# Rfid.net
KiCad netlist of a schematic drawn in EAGLE
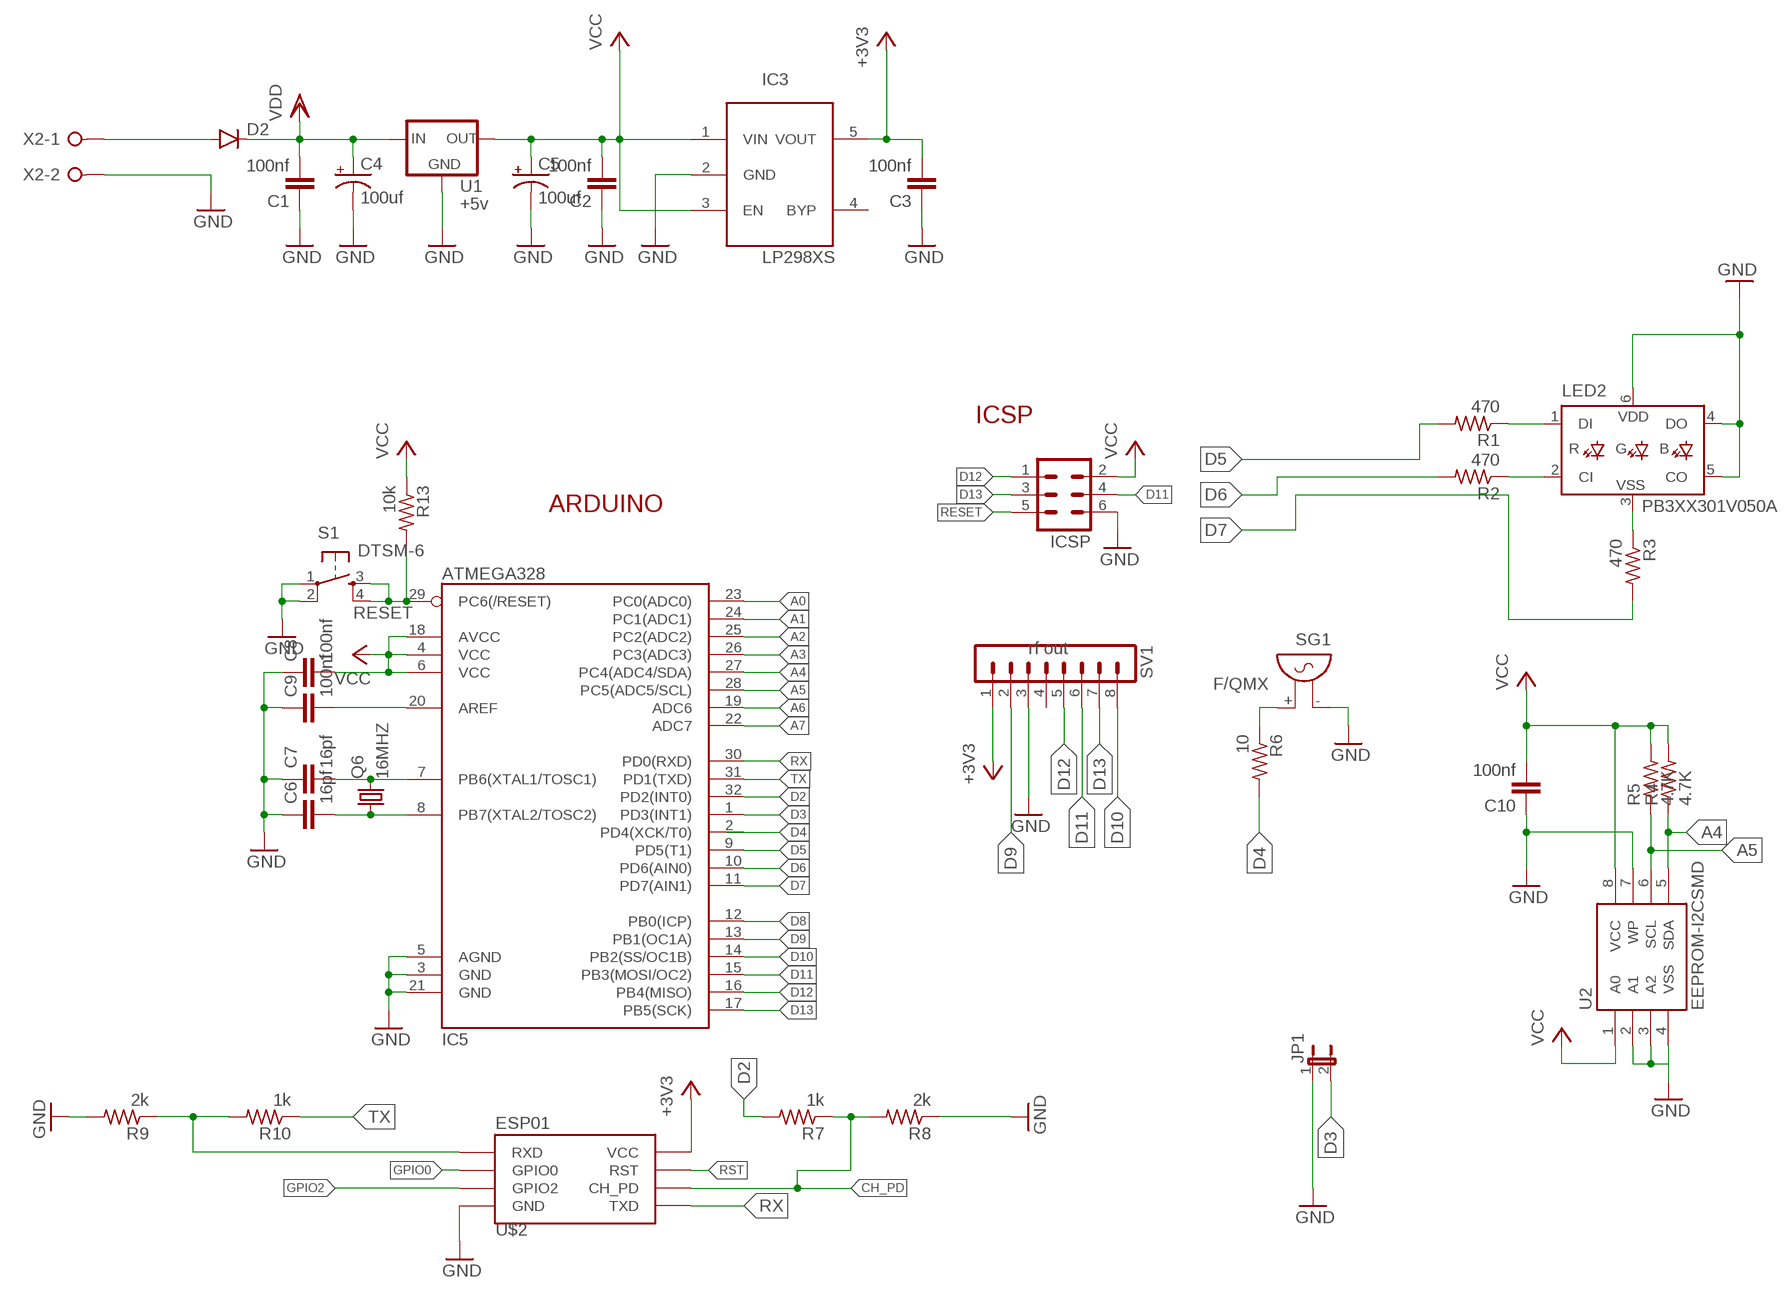
[diagram p0: schematic, sheet 1]

(export (version "E")
  (design (tool "Eeschema 10.0.6"))
  (components
    (comp (ref "C1")
      (value "100nf")
      (footprint "eagle-import:C0805")
      (libsource (lib "eagle-import") (part "C-EUC0805"))
    )
    (comp (ref "C2")
      (value "100nf")
      (footprint "eagle-import:C0805")
      (libsource (lib "eagle-import") (part "C-EUC0805"))
    )
    (comp (ref "C3")
      (value "100nf")
      (footprint "eagle-import:C0805")
      (libsource (lib "eagle-import") (part "C-EUC0805"))
    )
    (comp (ref "C4")
      (value "100uf")
      (footprint "eagle-import:PANASONIC_D")
      (libsource (lib "eagle-import") (part "CAP_POLD"))
    )
    (comp (ref "C5")
      (value "100uf")
      (footprint "eagle-import:PANASONIC_D")
      (libsource (lib "eagle-import") (part "CAP_POLD"))
    )
    (comp (ref "C6")
      (value "16pf")
      (footprint "eagle-import:C0805")
      (libsource (lib "eagle-import") (part "C-EUC0805"))
    )
    (comp (ref "C7")
      (value "16pf")
      (footprint "eagle-import:C0805")
      (libsource (lib "eagle-import") (part "C-EUC0805"))
    )
    (comp (ref "C8")
      (value "100nf")
      (footprint "eagle-import:C0805")
      (libsource (lib "eagle-import") (part "C-EUC0805"))
    )
    (comp (ref "C9")
      (value "100nf")
      (footprint "eagle-import:C0805")
      (libsource (lib "eagle-import") (part "C-EUC0805"))
    )
    (comp (ref "C10")
      (value "100nf")
      (footprint "eagle-import:C0805")
      (libsource (lib "eagle-import") (part "C-EUC0805"))
    )
    (comp (ref "D2")
      (value "DIODESMA-ALT")
      (footprint "eagle-import:SMA-DIODE_ALT")
      (libsource (lib "eagle-import") (part "DIODESMA-ALT"))
    )
    (comp (ref "IC3")
      (value "LP298XS")
      (footprint "eagle-import:SOT23-5L")
      (libsource (lib "eagle-import") (part "LP298XS"))
    )
    (comp (ref "IC5")
      (value "ATMEGA328")
      (footprint "eagle-import:TQFP32-08")
      (libsource (lib "eagle-import") (part "ATMEGA168"))
    )
    (comp (ref "ICSP")
      (value "ML6")
      (footprint "eagle-import:ML6")
      (libsource (lib "eagle-import") (part "ML6"))
    )
    (comp (ref "JP1")
      (value "JUMPER-2PTH")
      (footprint "eagle-import:1X02")
      (libsource (lib "eagle-import") (part "JUMPER-2PTH"))
    )
    (comp (ref "LED2")
      (value "PB3XX301V050A")
      (footprint "eagle-import:PB3XX301V050A")
      (libsource (lib "eagle-import") (part "PB3XX301V050A"))
    )
    (comp (ref "Q6")
      (value "16MHZ")
      (footprint "eagle-import:HC49_S")
      (libsource (lib "eagle-import") (part "CRYSTALHC49S"))
    )
    (comp (ref "R1")
      (value "470")
      (footprint "eagle-import:R0805")
      (libsource (lib "eagle-import") (part "R-US_R0805"))
    )
    (comp (ref "R2")
      (value "470")
      (footprint "eagle-import:R0805")
      (libsource (lib "eagle-import") (part "R-US_R0805"))
    )
    (comp (ref "R3")
      (value "470")
      (footprint "eagle-import:R0805")
      (libsource (lib "eagle-import") (part "R-US_R0805"))
    )
    (comp (ref "R4")
      (value "4.7K")
      (footprint "eagle-import:R0805")
      (libsource (lib "eagle-import") (part "R-US_R0805"))
    )
    (comp (ref "R5")
      (value "4.7K")
      (footprint "eagle-import:R0805")
      (libsource (lib "eagle-import") (part "R-US_R0805"))
    )
    (comp (ref "R6")
      (value "10")
      (footprint "eagle-import:R0805")
      (libsource (lib "eagle-import") (part "R-US_R0805"))
    )
    (comp (ref "R7")
      (value "1k")
      (footprint "eagle-import:R0805")
      (libsource (lib "eagle-import") (part "R-US_R0805"))
    )
    (comp (ref "R8")
      (value "2k")
      (footprint "eagle-import:R0805")
      (libsource (lib "eagle-import") (part "R-US_R0805"))
    )
    (comp (ref "R9")
      (value "2k")
      (footprint "eagle-import:R0805")
      (libsource (lib "eagle-import") (part "R-US_R0805"))
    )
    (comp (ref "R10")
      (value "1k")
      (footprint "eagle-import:R0805")
      (libsource (lib "eagle-import") (part "R-US_R0805"))
    )
    (comp (ref "R13")
      (value "10k")
      (footprint "eagle-import:R0805")
      (libsource (lib "eagle-import") (part "R-US_R0805"))
    )
    (comp (ref "S1")
      (value "DTSM-6")
      (footprint "eagle-import:DTSM-6")
      (libsource (lib "eagle-import") (part "DTSM-6"))
    )
    (comp (ref "SG1")
      (value "F/QMX")
      (footprint "eagle-import:F_QMX")
      (libsource (lib "eagle-import") (part "F/QMX"))
    )
    (comp (ref "SV1")
      (value "MA08-1")
      (footprint "eagle-import:MA08-1")
      (libsource (lib "eagle-import") (part "MA08-1"))
    )
    (comp (ref "U$2")
      (value "ESP01")
      (footprint "eagle-import:ESP01")
      (libsource (lib "eagle-import") (part "ESP01"))
    )
    (comp (ref "U1")
      (value "+5v")
      (footprint "eagle-import:TO-252")
      (libsource (lib "eagle-import") (part "V_REG_78XX7812"))
    )
    (comp (ref "U2")
      (value "EEPROM-I2CSMD")
      (footprint "eagle-import:SO08")
      (libsource (lib "eagle-import") (part "EEPROM-I2CSMD"))
    )
    (comp (ref "X2")
      (value "W237-02P")
      (footprint "eagle-import:W237-132")
      (libsource (lib "eagle-import") (part "W237-02P"))
    )
  )
  (nets
    (net (code "1") (name "+3V3") (class "Default")
      (node (ref "C3") (pin "2") (pinfunction "2_2") (pintype "passive"))
      (node (ref "IC3") (pin "5") (pinfunction "VOUT_5") (pintype "bidirectional"))
      (node (ref "SV1") (pin "1") (pinfunction "1_1") (pintype "passive"))
      (node (ref "U$2") (pin "VCC") (pinfunction "VCC_VCC") (pintype "bidirectional"))
    )
    (net (code "2") (name "A0") (class "Default")
      (node (ref "IC5") (pin "23") (pinfunction "PC0(ADC0)_23") (pintype "bidirectional"))
    )
    (net (code "3") (name "A1") (class "Default")
      (node (ref "IC5") (pin "24") (pinfunction "PC1(ADC1)_24") (pintype "bidirectional"))
    )
    (net (code "4") (name "A2") (class "Default")
      (node (ref "IC5") (pin "25") (pinfunction "PC2(ADC2)_25") (pintype "bidirectional"))
    )
    (net (code "5") (name "A3") (class "Default")
      (node (ref "IC5") (pin "26") (pinfunction "PC3(ADC3)_26") (pintype "bidirectional"))
    )
    (net (code "6") (name "A4") (class "Default")
      (node (ref "IC5") (pin "27") (pinfunction "PC4(ADC4/SDA)_27") (pintype "bidirectional"))
      (node (ref "R4") (pin "1") (pinfunction "1_1") (pintype "passive"))
      (node (ref "U2") (pin "5") (pinfunction "SDA_5") (pintype "bidirectional"))
    )
    (net (code "7") (name "A5") (class "Default")
      (node (ref "IC5") (pin "28") (pinfunction "PC5(ADC5/SCL)_28") (pintype "bidirectional"))
      (node (ref "R5") (pin "1") (pinfunction "1_1") (pintype "passive"))
      (node (ref "U2") (pin "6") (pinfunction "SCL_6") (pintype "bidirectional"))
    )
    (net (code "8") (name "A6") (class "Default")
      (node (ref "IC5") (pin "19") (pinfunction "ADC6_19") (pintype "bidirectional"))
    )
    (net (code "9") (name "A7") (class "Default")
      (node (ref "IC5") (pin "22") (pinfunction "ADC7_22") (pintype "bidirectional"))
    )
    (net (code "10") (name "CH_PD") (class "Default")
      (node (ref "R7") (pin "1") (pinfunction "1_1") (pintype "passive"))
      (node (ref "R8") (pin "2") (pinfunction "2_2") (pintype "passive"))
      (node (ref "U$2") (pin "CH_PD") (pinfunction "CH_PD_CH_PD") (pintype "bidirectional"))
    )
    (net (code "11") (name "D2") (class "Default")
      (node (ref "IC5") (pin "32") (pinfunction "PD2(INT0)_32") (pintype "bidirectional"))
      (node (ref "R7") (pin "2") (pinfunction "2_2") (pintype "passive"))
    )
    (net (code "12") (name "D3") (class "Default")
      (node (ref "IC5") (pin "1") (pinfunction "PD3(INT1)_1") (pintype "bidirectional"))
      (node (ref "JP1") (pin "2") (pinfunction "2_2") (pintype "passive"))
    )
    (net (code "13") (name "D4") (class "Default")
      (node (ref "IC5") (pin "2") (pinfunction "PD4(XCK/T0)_2") (pintype "bidirectional"))
      (node (ref "R6") (pin "2") (pinfunction "2_2") (pintype "passive"))
    )
    (net (code "14") (name "D5") (class "Default")
      (node (ref "IC5") (pin "9") (pinfunction "PD5(T1)_9") (pintype "bidirectional"))
      (node (ref "R1") (pin "2") (pinfunction "2_2") (pintype "passive"))
    )
    (net (code "15") (name "D6") (class "Default")
      (node (ref "IC5") (pin "10") (pinfunction "PD6(AIN0)_10") (pintype "bidirectional"))
      (node (ref "R2") (pin "2") (pinfunction "2_2") (pintype "passive"))
    )
    (net (code "16") (name "D7") (class "Default")
      (node (ref "IC5") (pin "11") (pinfunction "PD7(AIN1)_11") (pintype "bidirectional"))
      (node (ref "R3") (pin "2") (pinfunction "2_2") (pintype "passive"))
    )
    (net (code "17") (name "D8") (class "Default")
      (node (ref "IC5") (pin "12") (pinfunction "PB0(ICP)_12") (pintype "bidirectional"))
    )
    (net (code "18") (name "D9") (class "Default")
      (node (ref "IC5") (pin "13") (pinfunction "PB1(OC1A)_13") (pintype "bidirectional"))
      (node (ref "SV1") (pin "2") (pinfunction "2_2") (pintype "passive"))
    )
    (net (code "19") (name "D10") (class "Default")
      (node (ref "IC5") (pin "14") (pinfunction "PB2(SS/OC1B)_14") (pintype "bidirectional"))
      (node (ref "SV1") (pin "8") (pinfunction "8_8") (pintype "passive"))
    )
    (net (code "20") (name "D11") (class "Default")
      (node (ref "IC5") (pin "15") (pinfunction "PB3(MOSI/OC2)_15") (pintype "bidirectional"))
      (node (ref "ICSP") (pin "4") (pinfunction "4_4") (pintype "passive"))
      (node (ref "SV1") (pin "6") (pinfunction "6_6") (pintype "passive"))
    )
    (net (code "21") (name "D12") (class "Default")
      (node (ref "IC5") (pin "16") (pinfunction "PB4(MISO)_16") (pintype "bidirectional"))
      (node (ref "ICSP") (pin "1") (pinfunction "1_1") (pintype "passive"))
      (node (ref "SV1") (pin "5") (pinfunction "5_5") (pintype "passive"))
    )
    (net (code "22") (name "D13") (class "Default")
      (node (ref "IC5") (pin "17") (pinfunction "PB5(SCK)_17") (pintype "bidirectional"))
      (node (ref "ICSP") (pin "3") (pinfunction "3_3") (pintype "passive"))
      (node (ref "SV1") (pin "7") (pinfunction "7_7") (pintype "passive"))
    )
    (net (code "23") (name "GND") (class "Default")
      (node (ref "C1") (pin "1") (pinfunction "1_1") (pintype "passive"))
      (node (ref "C10") (pin "1") (pinfunction "1_1") (pintype "passive"))
      (node (ref "C2") (pin "1") (pinfunction "1_1") (pintype "passive"))
      (node (ref "C3") (pin "1") (pinfunction "1_1") (pintype "passive"))
      (node (ref "C4") (pin "-") (pinfunction "-_-") (pintype "passive"))
      (node (ref "C5") (pin "-") (pinfunction "-_-") (pintype "passive"))
      (node (ref "C6") (pin "1") (pinfunction "1_1") (pintype "passive"))
      (node (ref "C7") (pin "1") (pinfunction "1_1") (pintype "passive"))
      (node (ref "C8") (pin "1") (pinfunction "1_1") (pintype "passive"))
      (node (ref "C9") (pin "1") (pinfunction "1_1") (pintype "passive"))
      (node (ref "IC3") (pin "2") (pinfunction "GND_2") (pintype "bidirectional"))
      (node (ref "IC5") (pin "21") (pinfunction "GND_21") (pintype "bidirectional"))
      (node (ref "IC5") (pin "3") (pinfunction "GND_3") (pintype "bidirectional"))
      (node (ref "IC5") (pin "5") (pinfunction "AGND_5") (pintype "bidirectional"))
      (node (ref "ICSP") (pin "6") (pinfunction "6_6") (pintype "passive"))
      (node (ref "JP1") (pin "1") (pinfunction "1_1") (pintype "passive"))
      (node (ref "LED2") (pin "4") (pinfunction "DO_4") (pintype "output"))
      (node (ref "LED2") (pin "5") (pinfunction "CO_5") (pintype "output"))
      (node (ref "LED2") (pin "6") (pinfunction "VDD_6") (pintype "power_in"))
      (node (ref "R8") (pin "1") (pinfunction "1_1") (pintype "passive"))
      (node (ref "R9") (pin "2") (pinfunction "2_2") (pintype "passive"))
      (node (ref "S1") (pin "1") (pinfunction "1_1") (pintype "passive"))
      (node (ref "S1") (pin "2") (pinfunction "2_2") (pintype "passive"))
      (node (ref "SG1") (pin "-") (pinfunction "1_-") (pintype "passive"))
      (node (ref "SV1") (pin "3") (pinfunction "3_3") (pintype "passive"))
      (node (ref "U$2") (pin "GND") (pinfunction "GND_GND") (pintype "bidirectional"))
      (node (ref "U1") (pin "3") (pinfunction "GND_3") (pintype "input"))
      (node (ref "U2") (pin "2") (pinfunction "A1_2") (pintype "bidirectional"))
      (node (ref "U2") (pin "3") (pinfunction "A2_3") (pintype "bidirectional"))
      (node (ref "U2") (pin "4") (pinfunction "VSS_4") (pintype "power_in"))
      (node (ref "U2") (pin "7") (pinfunction "WP_7") (pintype "bidirectional"))
      (node (ref "X2") (pin "2") (pinfunction "KL_2") (pintype "passive"))
    )
    (net (code "24") (name "GPIO0") (class "Default")
      (node (ref "U$2") (pin "GPIO0") (pinfunction "GPIO0_GPIO0") (pintype "bidirectional"))
    )
    (net (code "25") (name "GPIO2") (class "Default")
      (node (ref "U$2") (pin "GPIO2") (pinfunction "GPIO2_GPIO2") (pintype "bidirectional"))
    )
    (net (code "26") (name "Net-(IC5-AREF)") (class "Default")
      (node (ref "C9") (pin "2") (pinfunction "2_2") (pintype "passive"))
      (node (ref "IC5") (pin "20") (pinfunction "AREF_20") (pintype "bidirectional"))
    )
    (net (code "27") (name "Net-(IC5-PB6(XTAL1{slash}TOSC1))") (class "Default")
      (node (ref "C7") (pin "2") (pinfunction "2_2") (pintype "passive"))
      (node (ref "IC5") (pin "7") (pinfunction "PB6(XTAL1/TOSC1)_7") (pintype "bidirectional"))
      (node (ref "Q6") (pin "2") (pinfunction "2_2") (pintype "passive"))
    )
    (net (code "28") (name "Net-(IC5-PB7(XTAL2{slash}TOSC2))") (class "Default")
      (node (ref "C6") (pin "2") (pinfunction "2_2") (pintype "passive"))
      (node (ref "IC5") (pin "8") (pinfunction "PB7(XTAL2/TOSC2)_8") (pintype "bidirectional"))
      (node (ref "Q6") (pin "1") (pinfunction "1_1") (pintype "passive"))
    )
    (net (code "29") (name "Net-(LED2-CI)") (class "Default")
      (node (ref "LED2") (pin "2") (pinfunction "CI_2") (pintype "input"))
      (node (ref "R2") (pin "1") (pinfunction "1_1") (pintype "passive"))
    )
    (net (code "30") (name "Net-(LED2-DI)") (class "Default")
      (node (ref "LED2") (pin "1") (pinfunction "DI_1") (pintype "input"))
      (node (ref "R1") (pin "1") (pinfunction "1_1") (pintype "passive"))
    )
    (net (code "31") (name "Net-(LED2-VSS)") (class "Default")
      (node (ref "LED2") (pin "3") (pinfunction "VSS_3") (pintype "power_in"))
      (node (ref "R3") (pin "1") (pinfunction "1_1") (pintype "passive"))
    )
    (net (code "32") (name "Net-(SG1-2)") (class "Default")
      (node (ref "R6") (pin "1") (pinfunction "1_1") (pintype "passive"))
      (node (ref "SG1") (pin "+") (pinfunction "2_+") (pintype "passive"))
    )
    (net (code "33") (name "Net-(U$2-RXD)") (class "Default")
      (node (ref "R10") (pin "2") (pinfunction "2_2") (pintype "passive"))
      (node (ref "R9") (pin "1") (pinfunction "1_1") (pintype "passive"))
      (node (ref "U$2") (pin "RX") (pinfunction "RXD_RX") (pintype "bidirectional"))
    )
    (net (code "34") (name "Net-(X2A-KL)") (class "Default")
      (node (ref "D2") (pin "A") (pinfunction "A_A") (pintype "passive"))
      (node (ref "X2") (pin "1") (pinfunction "KL_1") (pintype "passive"))
    )
    (net (code "35") (name "RESET") (class "Default")
      (node (ref "IC5") (pin "29") (pinfunction "PC6(/RESET)_29") (pintype "bidirectional"))
      (node (ref "ICSP") (pin "5") (pinfunction "5_5") (pintype "passive"))
      (node (ref "R13") (pin "2") (pinfunction "2_2") (pintype "passive"))
      (node (ref "S1") (pin "3") (pinfunction "3_3") (pintype "passive"))
      (node (ref "S1") (pin "4") (pinfunction "4_4") (pintype "passive"))
    )
    (net (code "36") (name "RST") (class "Default")
      (node (ref "U$2") (pin "RST") (pinfunction "RST_RST") (pintype "bidirectional"))
    )
    (net (code "37") (name "RX") (class "Default")
      (node (ref "IC5") (pin "30") (pinfunction "PD0(RXD)_30") (pintype "bidirectional"))
      (node (ref "U$2") (pin "TX") (pinfunction "TXD_TX") (pintype "bidirectional"))
    )
    (net (code "38") (name "TX") (class "Default")
      (node (ref "IC5") (pin "31") (pinfunction "PD1(TXD)_31") (pintype "bidirectional"))
      (node (ref "R10") (pin "1") (pinfunction "1_1") (pintype "passive"))
    )
    (net (code "39") (name "VCC") (class "Default")
      (node (ref "C10") (pin "2") (pinfunction "2_2") (pintype "passive"))
      (node (ref "C2") (pin "2") (pinfunction "2_2") (pintype "passive"))
      (node (ref "C5") (pin "+") (pinfunction "+_+") (pintype "passive"))
      (node (ref "C8") (pin "2") (pinfunction "2_2") (pintype "passive"))
      (node (ref "IC3") (pin "1") (pinfunction "VIN_1") (pintype "bidirectional"))
      (node (ref "IC3") (pin "3") (pinfunction "EN_3") (pintype "bidirectional"))
      (node (ref "IC5") (pin "18") (pinfunction "AVCC_18") (pintype "bidirectional"))
      (node (ref "IC5") (pin "4") (pinfunction "VCC_4") (pintype "bidirectional"))
      (node (ref "IC5") (pin "6") (pinfunction "VCC_6") (pintype "bidirectional"))
      (node (ref "ICSP") (pin "2") (pinfunction "2_2") (pintype "passive"))
      (node (ref "R13") (pin "1") (pinfunction "1_1") (pintype "passive"))
      (node (ref "R4") (pin "2") (pinfunction "2_2") (pintype "passive"))
      (node (ref "R5") (pin "2") (pinfunction "2_2") (pintype "passive"))
      (node (ref "U1") (pin "2") (pinfunction "OUT_2") (pintype "passive"))
      (node (ref "U2") (pin "1") (pinfunction "A0_1") (pintype "bidirectional"))
      (node (ref "U2") (pin "8") (pinfunction "VCC_8") (pintype "power_in"))
    )
    (net (code "40") (name "VDD") (class "Default")
      (node (ref "C1") (pin "2") (pinfunction "2_2") (pintype "passive"))
      (node (ref "C4") (pin "+") (pinfunction "+_+") (pintype "passive"))
      (node (ref "D2") (pin "C") (pinfunction "C_C") (pintype "passive"))
      (node (ref "U1") (pin "1") (pinfunction "IN_1") (pintype "input"))
    )
    (net (code "41") (name "unconnected-(IC3-BYP-Pad4)") (class "Default")
      (node (ref "IC3") (pin "4") (pinfunction "BYP_4") (pintype "bidirectional"))
    )
    (net (code "42") (name "unconnected-(SV1-Pad4)") (class "Default")
      (node (ref "SV1") (pin "4") (pinfunction "4_4") (pintype "passive"))
    )
  )
)
